# LED_Microcontroller_LED_schematic.net
KiCad netlist of a schematic drawn in Altium Designer
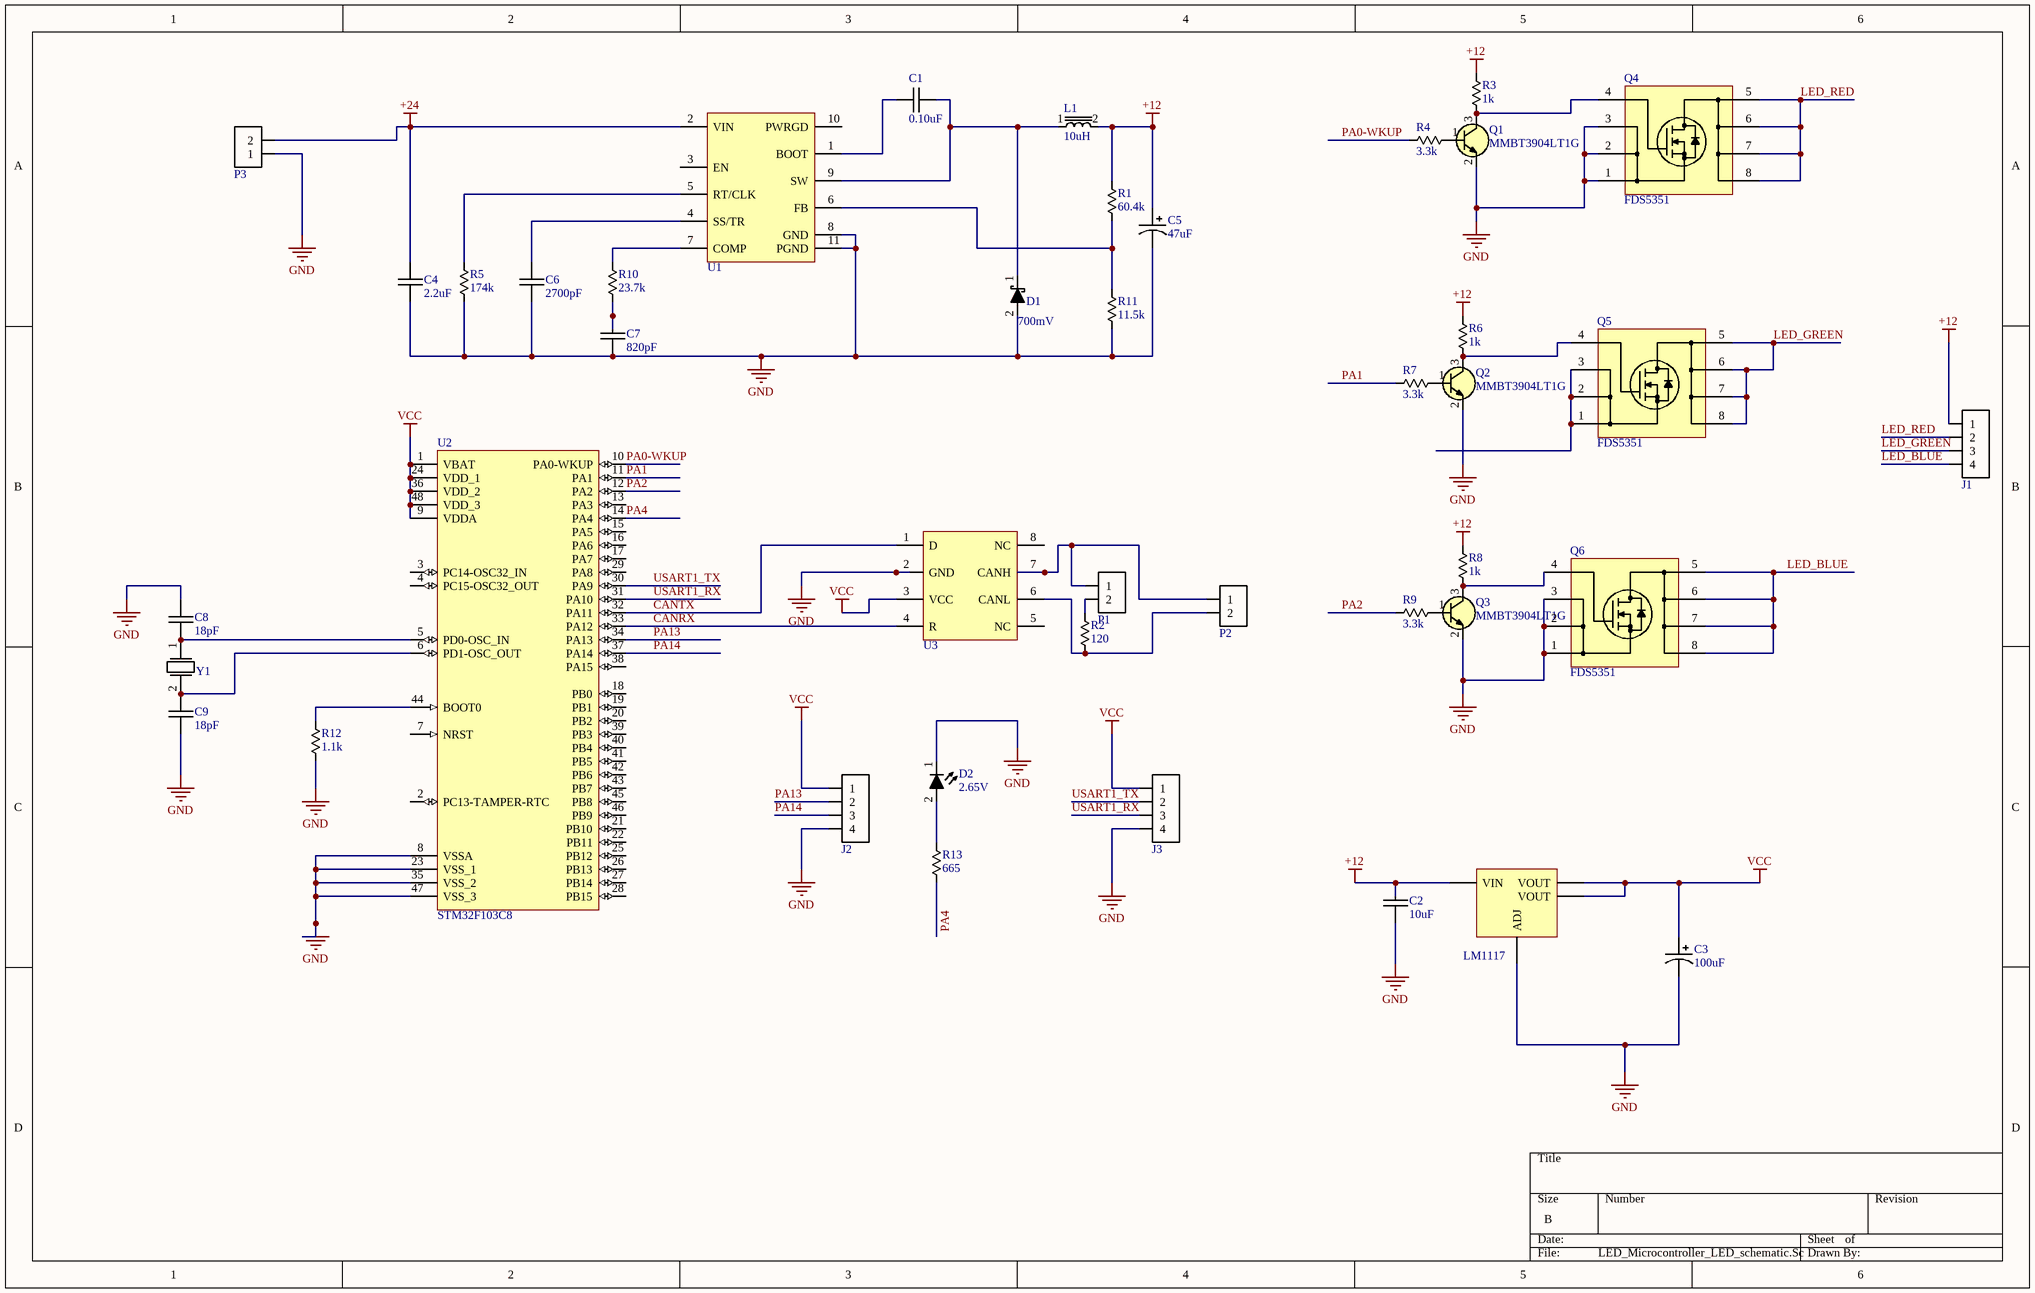
[diagram p0: LED_Microcontroller_LED_schematic.SchDoc]

(export (version "E")
  (design (tool "Eeschema 10.0.6"))
  (components
    (comp (ref "C1")
      (value "0.10uF")
      (footprint "chip_0805")
      (description "CAP, 0.10uF, 10%, 16V, X7R, 0805")
      (fields (field (name "PART NUMBER") "CAP-00069") (field (name "TOLERANCE") "10%"))
      (libsource (lib "Capacitors$") (part "CAP-00069"))
    )
    (comp (ref "C2")
      (value "10uF")
      (footprint "chip_1206")
      (description "CAP, 10uF, ±10%, 25V, X7R, 1206")
      (fields (field (name "PART NUMBER") "CAP-00539") (field (name "TOLERANCE") "±10%"))
      (libsource (lib "Capacitors$") (part "CAP-00539"))
    )
    (comp (ref "C3")
      (value "100uF")
      (footprint "chip_2917_AVX_TAJD")
      (description "CAP, 100uF, ±10%, 16V, Tantalum, 2917")
      (fields (field (name "PART NUMBER") "CAP-00550") (field (name "TOLERANCE") "±10%"))
      (libsource (lib "Capacitors$") (part "CAP-00550"))
    )
    (comp (ref "C4")
      (value "2.2uF")
      (footprint "chip_0603")
      (description "CAP, 2.2uF, ±10%, 10V, X7R, 0603")
      (fields (field (name "PART NUMBER") "CAP-00512") (field (name "TOLERANCE") "±10%"))
      (libsource (lib "Capacitors$") (part "CAP-00512"))
    )
    (comp (ref "C5")
      (value "47uF")
      (footprint "CP_NICHICON_UUX_10x10")
      (description "CAP, 47uF, ±20%, 100V, Al, SMD")
      (fields (field (name "PART NUMBER") "CAP-00567") (field (name "TOLERANCE") "±20%"))
      (libsource (lib "Capacitors$") (part "CAP-00567"))
    )
    (comp (ref "C6")
      (value "2700pF")
      (footprint "chip_0805")
      (description "CAP, 2700pF, 10%, 50V, X7R, 0805")
      (fields (field (name "PART NUMBER") "CAP-00024") (field (name "TOLERANCE") "10%"))
      (libsource (lib "Capacitors$") (part "CAP-00024"))
    )
    (comp (ref "C7")
      (value "820pF")
      (footprint "chip_0805")
      (description "CAP, 820pF, 10%, 50V, X7R, 0805")
      (fields (field (name "PART NUMBER") "CAP-00008") (field (name "TOLERANCE") "10%"))
      (libsource (lib "Capacitors$") (part "CAP-00008"))
    )
    (comp (ref "C8")
      (value "18pF")
      (footprint "chip_0603")
      (description "CAP, 18pF, ±2%, 50V, C0G, 0603")
      (fields (field (name "PART NUMBER") "CAP-00409") (field (name "TOLERANCE") "±2%"))
      (libsource (lib "Capacitors$") (part "CAP-00409"))
    )
    (comp (ref "C9")
      (value "18pF")
      (footprint "chip_0603")
      (description "CAP, 18pF, ±2%, 50V, C0G, 0603")
      (fields (field (name "PART NUMBER") "CAP-00409") (field (name "TOLERANCE") "±2%"))
      (libsource (lib "Capacitors$") (part "CAP-00409"))
    )
    (comp (ref "D1")
      (value "700mV")
      (footprint "do-214ab")
      (description "Dio, Schottky, 5A, 700mV, 60V, SMC")
      (fields (field (name "PART NUMBER") "DIO-00048") (field (name "MANUFACTURER") "Diodes Incorporated"))
      (libsource (lib "Diodes$") (part "DIO-00048"))
    )
    (comp (ref "D2")
      (value "2.65V")
      (footprint "chip_0603_LED")
      (description "LED, Green, 0603, Low current, HELI2 Series")
      (fields (field (name "PART NUMBER") "DIO-00050") (field (name "MANUFACTURER") "Kingbright"))
      (libsource (lib "Diodes$") (part "DIO-00050"))
    )
    (comp (ref "J1")
      (value "conn-4x1_0")
      (footprint "TERM_3.50MM_4x1_0")
      (description "Term Blk, 4 Pos, 8A, 3.5mm Pitch, Screwless")
      (fields (field (name "PART NUMBER") "CONN-00024") (field (name "MANUFACTURER") "Phoenix Contact"))
      (libsource (lib "Connectors$") (part "CONN-00024"))
    )
    (comp (ref "J2")
      (value "conn-4x1_0")
      (footprint "HDDR_4x1_0")
      (description "Header 4x1, 0.1\"")
      (fields (field (name "PART NUMBER") "CONN-00029"))
      (libsource (lib "Connectors$") (part "CONN-00029"))
    )
    (comp (ref "J3")
      (value "conn-4x1_0")
      (footprint "HDDR_4x1_0")
      (description "Header 4x1, 0.1\"")
      (fields (field (name "PART NUMBER") "CONN-00029"))
      (libsource (lib "Connectors$") (part "CONN-00029"))
    )
    (comp (ref "L1")
      (value "ind_1")
      (footprint "VISHAY_IHLP3232DZ")
      (description "Ind, 10uH, 20%, 5.2A (9A sat.), 0.0599 Ohm")
      (fields
        (field (name "PART NUMBER") "MAG-00106")
        (field (name "INDUCTANCE") "10uH")
        (field (name "TOLERANCE") "20%")
      )
      (libsource (lib "Magnetics$") (part "MAG-00106"))
    )
    (comp (ref "LM1117")
      (value "LM1117")
      (footprint "sot-223-4")
      (description "REG, Linear, Fixed 3V3, 800mA, SOT-223")
      (fields (field (name "PART NUMBER") "PWREG-00018") (field (name "MANUFACTURER") "TI"))
      (libsource (lib "Power Reg$") (part "PWREG-00018"))
    )
    (comp (ref "P1")
      (value "conn-2x1_0")
      (footprint "HDDR_2x1_0")
      (description "Header, 2x1, 0.1\"")
      (fields (field (name "PART NUMBER") "CONN-00055") (field (name "MANUFACTURER") "Samtec"))
      (libsource (lib "Connectors$") (part "CONN-00055"))
    )
    (comp (ref "P2")
      (value "conn-2x1_0")
      (footprint "TERM_3.50MM_2x1_0")
      (description "Term Blk, 2 Pos, 8A, 3.5mm Pitch, Screwless")
      (fields (field (name "PART NUMBER") "CONN-00023") (field (name "MANUFACTURER") "Phoenix Contact"))
      (libsource (lib "Connectors$") (part "CONN-00023"))
    )
    (comp (ref "P3")
      (value "conn-2x1_0")
      (footprint "TERM_3.50MM_2x1_0")
      (description "Term Blk, 2 Pos, 8A, 3.5mm Pitch, Screwless")
      (fields (field (name "PART NUMBER") "CONN-00023") (field (name "MANUFACTURER") "Phoenix Contact"))
      (libsource (lib "Connectors$") (part "CONN-00023"))
    )
    (comp (ref "Q1")
      (value "MMBT3904LT1G")
      (footprint "SOT-23-3_1")
      (description "XSTR, NPN, 200mA, 40V, Vce 0.3V, SOT-23-3")
      (fields (field (name "PART NUMBER") "XSTR-00037") (field (name "MANUFACTURER") "ON Semi"))
      (libsource (lib "Transistors$") (part "XSTR-00037"))
    )
    (comp (ref "Q2")
      (value "MMBT3904LT1G")
      (footprint "SOT-23-3_1")
      (description "XSTR, NPN, 200mA, 40V, Vce 0.3V, SOT-23-3")
      (fields (field (name "PART NUMBER") "XSTR-00037") (field (name "MANUFACTURER") "ON Semi"))
      (libsource (lib "Transistors$") (part "XSTR-00037"))
    )
    (comp (ref "Q3")
      (value "MMBT3904LT1G")
      (footprint "SOT-23-3_1")
      (description "XSTR, NPN, 200mA, 40V, Vce 0.3V, SOT-23-3")
      (fields (field (name "PART NUMBER") "XSTR-00037") (field (name "MANUFACTURER") "ON Semi"))
      (libsource (lib "Transistors$") (part "XSTR-00037"))
    )
    (comp (ref "Q4")
      (value "FDS5351")
      (footprint "SO-8")
      (description "XSTR NFET, 6.1A, 60V, 5W, SOIC-8")
      (fields (field (name "PART NUMBER") "XSTR-00034") (field (name "MANUFACTURER") "ON Semi"))
      (libsource (lib "Transistors$") (part "XSTR-00034"))
    )
    (comp (ref "Q5")
      (value "FDS5351")
      (footprint "SO-8")
      (description "XSTR NFET, 6.1A, 60V, 5W, SOIC-8")
      (fields (field (name "PART NUMBER") "XSTR-00034") (field (name "MANUFACTURER") "ON Semi"))
      (libsource (lib "Transistors$") (part "XSTR-00034"))
    )
    (comp (ref "Q6")
      (value "FDS5351")
      (footprint "SO-8")
      (description "XSTR NFET, 6.1A, 60V, 5W, SOIC-8")
      (fields (field (name "PART NUMBER") "XSTR-00034") (field (name "MANUFACTURER") "ON Semi"))
      (libsource (lib "Transistors$") (part "XSTR-00034"))
    )
    (comp (ref "R1")
      (value "60.4k")
      (footprint "chip_0805")
      (description "RES SMD 60.4K OHM 1% 1/8W 0805")
      (fields (field (name "PART NUMBER") "RES-00531") (field (name "TOLERANCE") "1%"))
      (libsource (lib "Resistors$") (part "RES-00531"))
    )
    (comp (ref "R2")
      (value "120")
      (footprint "chip_0805")
      (description "RES SMD 120 OHM 1% 1/8W 0805")
      (fields (field (name "PART NUMBER") "RES-00183") (field (name "TOLERANCE") "1%"))
      (libsource (lib "Resistors$") (part "RES-00183"))
    )
    (comp (ref "R3")
      (value "1k")
      (footprint "chip_0805")
      (description "RES SMD 1K OHM 1% 1/8W 0805")
      (fields (field (name "PART NUMBER") "RES-00361") (field (name "TOLERANCE") "1%"))
      (libsource (lib "Resistors$") (part "RES-00361"))
    )
    (comp (ref "R4")
      (value "3.3k")
      (footprint "chip_0603")
      (description "RES SMD 3.3K OHM 1% 1/4W 0603")
      (fields (field (name "PART NUMBER") "RES-00419") (field (name "TOLERANCE") "1%"))
      (libsource (lib "Resistors$") (part "RES-00419"))
    )
    (comp (ref "R5")
      (value "174k")
      (footprint "chip_0805")
      (description "RES SMD 174K OHM 1% 1/8W 0805")
      (fields (field (name "PART NUMBER") "RES-00350") (field (name "TOLERANCE") "1%"))
      (libsource (lib "Resistors$") (part "RES-00350"))
    )
    (comp (ref "R6")
      (value "1k")
      (footprint "chip_0805")
      (description "RES SMD 1K OHM 1% 1/8W 0805")
      (fields (field (name "PART NUMBER") "RES-00361") (field (name "TOLERANCE") "1%"))
      (libsource (lib "Resistors$") (part "RES-00361"))
    )
    (comp (ref "R7")
      (value "3.3k")
      (footprint "chip_0603")
      (description "RES SMD 3.3K OHM 1% 1/4W 0603")
      (fields (field (name "PART NUMBER") "RES-00419") (field (name "TOLERANCE") "1%"))
      (libsource (lib "Resistors$") (part "RES-00419"))
    )
    (comp (ref "R8")
      (value "1k")
      (footprint "chip_0805")
      (description "RES SMD 1K OHM 1% 1/8W 0805")
      (fields (field (name "PART NUMBER") "RES-00361") (field (name "TOLERANCE") "1%"))
      (libsource (lib "Resistors$") (part "RES-00361"))
    )
    (comp (ref "R9")
      (value "3.3k")
      (footprint "chip_0603")
      (description "RES SMD 3.3K OHM 1% 1/4W 0603")
      (fields (field (name "PART NUMBER") "RES-00419") (field (name "TOLERANCE") "1%"))
      (libsource (lib "Resistors$") (part "RES-00419"))
    )
    (comp (ref "R10")
      (value "23.7k")
      (footprint "chip_0805")
      (description "RES SMD 23.7K OHM 1% 1/8W 0805")
      (fields (field (name "PART NUMBER") "RES-00392") (field (name "TOLERANCE") "1%"))
      (libsource (lib "Resistors$") (part "RES-00392"))
    )
    (comp (ref "R11")
      (value "11.5k")
      (footprint "chip_0805")
      (description "RES SMD 11.5K OHM 1% 1/8W 0805")
      (fields (field (name "PART NUMBER") "RES-00309") (field (name "TOLERANCE") "1%"))
      (libsource (lib "Resistors$") (part "RES-00309"))
    )
    (comp (ref "R12")
      (value "1.1k")
      (footprint "chip_0603")
      (description "RES SMD 1.1K OHM 1% 1/4W 0603")
      (fields (field (name "PART NUMBER") "RES-00264") (field (name "TOLERANCE") "1%"))
      (libsource (lib "Resistors$") (part "RES-00264"))
    )
    (comp (ref "R13")
      (value "665")
      (footprint "chip_0805")
      (description "RES SMD 665 OHM 1% 1/8W 0805")
      (fields (field (name "PART NUMBER") "RES-00248") (field (name "TOLERANCE") "1%"))
      (libsource (lib "Resistors$") (part "RES-00248"))
    )
    (comp (ref "U1")
      (value "TPS54561")
      (footprint "WSON-10_0")
      (description "REG, SW Buck Adj, 5A, 4.5-60V, 2.5MHz, TPS54561")
      (fields (field (name "PART NUMBER") "PWREG-00033") (field (name "MANUFACTURER") "TI"))
      (libsource (lib "Power Reg$") (part "PWREG-00033"))
    )
    (comp (ref "U2")
      (value "STM32F103C8")
      (footprint "LQFP48_0")
      (description "STM32 M3, LQFP-48")
      (fields (field (name "PART NUMBER") "UCTRL-00008") (field (name "MANUFACTURER") "ST"))
      (libsource (lib "Microcontrollers$") (part "UCTRL-00008"))
    )
    (comp (ref "U3")
      (value "SN65HVD232")
      (footprint "SO-8")
      (description "CANbus Transceiver, Single channel, SN65HVD232")
      (fields (field (name "PART NUMBER") "IFACE-00008") (field (name "MANUFACTURER") "TI"))
      (libsource (lib "Interfaces$") (part "IFACE-00008"))
    )
    (comp (ref "Y1")
      (value "osc_xtal_2p_0")
      (footprint "ABLS_AT49_OSC")
      (description "XTAL, 8MHz, 18pF, 20ppm")
      (fields (field (name "PART NUMBER") "OSC-00002") (field (name "TOLERANCE") "20ppm"))
      (libsource (lib "Oscillators$") (part "OSC-00002"))
    )
  )
  (nets
    (net (code "1") (name "+12") (class "Default")
      (node (ref "C2") (pin "1") (pinfunction "1_1") (pintype "passive"))
      (node (ref "C5") (pin "1") (pinfunction "1_1") (pintype "passive"))
      (node (ref "J1") (pin "1") (pinfunction "1_1") (pintype "passive"))
      (node (ref "L1") (pin "2") (pinfunction "2_2") (pintype "passive"))
      (node (ref "LM1117") (pin "3") (pinfunction "VIN_3") (pintype "passive"))
      (node (ref "R1") (pin "1") (pinfunction "1_1") (pintype "passive"))
      (node (ref "R3") (pin "1") (pinfunction "1_1") (pintype "passive"))
      (node (ref "R6") (pin "1") (pinfunction "1_1") (pintype "passive"))
      (node (ref "R8") (pin "1") (pinfunction "1_1") (pintype "passive"))
    )
    (net (code "2") (name "+24") (class "Default")
      (node (ref "C4") (pin "1") (pinfunction "1_1") (pintype "passive"))
      (node (ref "P3") (pin "2") (pinfunction "2_2") (pintype "passive"))
      (node (ref "U1") (pin "2") (pinfunction "VIN_2") (pintype "passive"))
    )
    (net (code "3") (name "/CANRX") (class "Default")
      (node (ref "U2") (pin "33") (pinfunction "PA12_33") (pintype "bidirectional"))
      (node (ref "U3") (pin "4") (pinfunction "R_4") (pintype "passive"))
    )
    (net (code "4") (name "/CANTX") (class "Default")
      (node (ref "U2") (pin "32") (pinfunction "PA11_32") (pintype "bidirectional"))
      (node (ref "U3") (pin "1") (pinfunction "D_1") (pintype "passive"))
    )
    (net (code "5") (name "/LED_BLUE") (class "Default")
      (node (ref "J1") (pin "4") (pinfunction "4_4") (pintype "passive"))
      (node (ref "Q6") (pin "5") (pinfunction "D_5") (pintype "passive"))
      (node (ref "Q6") (pin "6") (pinfunction "D_6") (pintype "passive"))
      (node (ref "Q6") (pin "7") (pinfunction "D_7") (pintype "passive"))
      (node (ref "Q6") (pin "8") (pinfunction "D_8") (pintype "passive"))
    )
    (net (code "6") (name "/LED_GREEN") (class "Default")
      (node (ref "J1") (pin "3") (pinfunction "3_3") (pintype "passive"))
      (node (ref "Q5") (pin "5") (pinfunction "D_5") (pintype "passive"))
      (node (ref "Q5") (pin "6") (pinfunction "D_6") (pintype "passive"))
      (node (ref "Q5") (pin "7") (pinfunction "D_7") (pintype "passive"))
      (node (ref "Q5") (pin "8") (pinfunction "D_8") (pintype "passive"))
    )
    (net (code "7") (name "/LED_RED") (class "Default")
      (node (ref "J1") (pin "2") (pinfunction "2_2") (pintype "passive"))
      (node (ref "Q4") (pin "5") (pinfunction "D_5") (pintype "passive"))
      (node (ref "Q4") (pin "6") (pinfunction "D_6") (pintype "passive"))
      (node (ref "Q4") (pin "7") (pinfunction "D_7") (pintype "passive"))
      (node (ref "Q4") (pin "8") (pinfunction "D_8") (pintype "passive"))
    )
    (net (code "8") (name "/PA0-WKUP") (class "Default")
      (node (ref "R4") (pin "2") (pinfunction "2_2") (pintype "passive"))
      (node (ref "U2") (pin "10") (pinfunction "PA0-WKUP_10") (pintype "bidirectional"))
    )
    (net (code "9") (name "/PA1") (class "Default")
      (node (ref "R7") (pin "2") (pinfunction "2_2") (pintype "passive"))
      (node (ref "U2") (pin "11") (pinfunction "PA1_11") (pintype "bidirectional"))
    )
    (net (code "10") (name "/PA2") (class "Default")
      (node (ref "R9") (pin "2") (pinfunction "2_2") (pintype "passive"))
      (node (ref "U2") (pin "12") (pinfunction "PA2_12") (pintype "bidirectional"))
    )
    (net (code "11") (name "/PA4") (class "Default")
      (node (ref "R13") (pin "2") (pinfunction "2_2") (pintype "passive"))
      (node (ref "U2") (pin "14") (pinfunction "PA4_14") (pintype "bidirectional"))
    )
    (net (code "12") (name "/PA13") (class "Default")
      (node (ref "J2") (pin "2") (pinfunction "2_2") (pintype "passive"))
      (node (ref "U2") (pin "34") (pinfunction "PA13_34") (pintype "bidirectional"))
    )
    (net (code "13") (name "/PA14") (class "Default")
      (node (ref "J2") (pin "3") (pinfunction "3_3") (pintype "passive"))
      (node (ref "U2") (pin "37") (pinfunction "PA14_37") (pintype "bidirectional"))
    )
    (net (code "14") (name "/USART1_RX") (class "Default")
      (node (ref "J3") (pin "3") (pinfunction "3_3") (pintype "passive"))
      (node (ref "U2") (pin "31") (pinfunction "PA10_31") (pintype "bidirectional"))
    )
    (net (code "15") (name "/USART1_TX") (class "Default")
      (node (ref "J3") (pin "2") (pinfunction "2_2") (pintype "passive"))
      (node (ref "U2") (pin "30") (pinfunction "PA9_30") (pintype "bidirectional"))
    )
    (net (code "16") (name "GND") (class "Default")
      (node (ref "C2") (pin "2") (pinfunction "2_2") (pintype "passive"))
      (node (ref "C3") (pin "2") (pinfunction "2_2") (pintype "passive"))
      (node (ref "C4") (pin "2") (pinfunction "2_2") (pintype "passive"))
      (node (ref "C5") (pin "2") (pinfunction "2_2") (pintype "passive"))
      (node (ref "C6") (pin "2") (pinfunction "2_2") (pintype "passive"))
      (node (ref "C7") (pin "2") (pinfunction "2_2") (pintype "passive"))
      (node (ref "C8") (pin "1") (pinfunction "1_1") (pintype "passive"))
      (node (ref "C9") (pin "2") (pinfunction "2_2") (pintype "passive"))
      (node (ref "D1") (pin "2") (pinfunction "2_2") (pintype "passive"))
      (node (ref "D2") (pin "1") (pinfunction "1_1") (pintype "passive"))
      (node (ref "J2") (pin "4") (pinfunction "4_4") (pintype "passive"))
      (node (ref "J3") (pin "4") (pinfunction "4_4") (pintype "passive"))
      (node (ref "LM1117") (pin "1") (pinfunction "ADJ_1") (pintype "passive"))
      (node (ref "P3") (pin "1") (pinfunction "1_1") (pintype "passive"))
      (node (ref "Q1") (pin "2") (pinfunction "E_2") (pintype "passive"))
      (node (ref "Q2") (pin "2") (pinfunction "E_2") (pintype "passive"))
      (node (ref "Q3") (pin "2") (pinfunction "E_2") (pintype "passive"))
      (node (ref "Q4") (pin "1") (pinfunction "S_1") (pintype "passive"))
      (node (ref "Q4") (pin "2") (pinfunction "S_2") (pintype "passive"))
      (node (ref "Q4") (pin "3") (pinfunction "S_3") (pintype "passive"))
      (node (ref "Q6") (pin "1") (pinfunction "S_1") (pintype "passive"))
      (node (ref "Q6") (pin "2") (pinfunction "S_2") (pintype "passive"))
      (node (ref "Q6") (pin "3") (pinfunction "S_3") (pintype "passive"))
      (node (ref "R11") (pin "2") (pinfunction "2_2") (pintype "passive"))
      (node (ref "R12") (pin "2") (pinfunction "2_2") (pintype "passive"))
      (node (ref "R5") (pin "2") (pinfunction "2_2") (pintype "passive"))
      (node (ref "U1") (pin "11") (pinfunction "PGND_11") (pintype "passive"))
      (node (ref "U1") (pin "8") (pinfunction "GND_8") (pintype "passive"))
      (node (ref "U2") (pin "23") (pinfunction "VSS_1_23") (pintype "power_in"))
      (node (ref "U2") (pin "35") (pinfunction "VSS_2_35") (pintype "power_in"))
      (node (ref "U2") (pin "47") (pinfunction "VSS_3_47") (pintype "power_in"))
      (node (ref "U2") (pin "8") (pinfunction "VSSA_8") (pintype "power_in"))
      (node (ref "U3") (pin "2") (pinfunction "GND_2") (pintype "passive"))
    )
    (net (code "17") (name "Net-(C7-Pad1)") (class "Default")
      (node (ref "C7") (pin "1") (pinfunction "1_1") (pintype "passive"))
      (node (ref "R10") (pin "2") (pinfunction "2_2") (pintype "passive"))
    )
    (net (code "18") (name "Net-(D2-Pad2)") (class "Default")
      (node (ref "D2") (pin "2") (pinfunction "2_2") (pintype "passive"))
      (node (ref "R13") (pin "1") (pinfunction "1_1") (pintype "passive"))
    )
    (net (code "19") (name "Net-(P1-Pad2)") (class "Default")
      (node (ref "P1") (pin "2") (pinfunction "2_2") (pintype "passive"))
      (node (ref "R2") (pin "1") (pinfunction "1_1") (pintype "passive"))
    )
    (net (code "20") (name "Net-(Q1-B)") (class "Default")
      (node (ref "Q1") (pin "1") (pinfunction "B_1") (pintype "passive"))
      (node (ref "R4") (pin "1") (pinfunction "1_1") (pintype "passive"))
    )
    (net (code "21") (name "Net-(Q1-C)") (class "Default")
      (node (ref "Q1") (pin "3") (pinfunction "C_3") (pintype "passive"))
      (node (ref "Q4") (pin "4") (pinfunction "G_4") (pintype "passive"))
      (node (ref "R3") (pin "2") (pinfunction "2_2") (pintype "passive"))
    )
    (net (code "22") (name "Net-(Q2-B)") (class "Default")
      (node (ref "Q2") (pin "1") (pinfunction "B_1") (pintype "passive"))
      (node (ref "R7") (pin "1") (pinfunction "1_1") (pintype "passive"))
    )
    (net (code "23") (name "Net-(Q2-C)") (class "Default")
      (node (ref "Q2") (pin "3") (pinfunction "C_3") (pintype "passive"))
      (node (ref "Q5") (pin "4") (pinfunction "G_4") (pintype "passive"))
      (node (ref "R6") (pin "2") (pinfunction "2_2") (pintype "passive"))
    )
    (net (code "24") (name "Net-(Q3-B)") (class "Default")
      (node (ref "Q3") (pin "1") (pinfunction "B_1") (pintype "passive"))
      (node (ref "R9") (pin "1") (pinfunction "1_1") (pintype "passive"))
    )
    (net (code "25") (name "Net-(Q3-C)") (class "Default")
      (node (ref "Q3") (pin "3") (pinfunction "C_3") (pintype "passive"))
      (node (ref "Q6") (pin "4") (pinfunction "G_4") (pintype "passive"))
      (node (ref "R8") (pin "2") (pinfunction "2_2") (pintype "passive"))
    )
    (net (code "26") (name "Net-(Q5-S-Pad1)") (class "Default")
      (node (ref "Q5") (pin "1") (pinfunction "S_1") (pintype "passive"))
      (node (ref "Q5") (pin "2") (pinfunction "S_2") (pintype "passive"))
      (node (ref "Q5") (pin "3") (pinfunction "S_3") (pintype "passive"))
    )
    (net (code "27") (name "Net-(U1-BOOT)") (class "Default")
      (node (ref "C1") (pin "2") (pinfunction "2_2") (pintype "passive"))
      (node (ref "U1") (pin "1") (pinfunction "BOOT_1") (pintype "passive"))
    )
    (net (code "28") (name "Net-(U1-COMP)") (class "Default")
      (node (ref "R10") (pin "1") (pinfunction "1_1") (pintype "passive"))
      (node (ref "U1") (pin "7") (pinfunction "COMP_7") (pintype "passive"))
    )
    (net (code "29") (name "Net-(U1-FB)") (class "Default")
      (node (ref "R1") (pin "2") (pinfunction "2_2") (pintype "passive"))
      (node (ref "R11") (pin "1") (pinfunction "1_1") (pintype "passive"))
      (node (ref "U1") (pin "6") (pinfunction "FB_6") (pintype "passive"))
    )
    (net (code "30") (name "Net-(U1-RT{slash}CLK)") (class "Default")
      (node (ref "R5") (pin "1") (pinfunction "1_1") (pintype "passive"))
      (node (ref "U1") (pin "5") (pinfunction "RT/CLK_5") (pintype "passive"))
    )
    (net (code "31") (name "Net-(U1-SS{slash}TR)") (class "Default")
      (node (ref "C6") (pin "1") (pinfunction "1_1") (pintype "passive"))
      (node (ref "U1") (pin "4") (pinfunction "SS/TR_4") (pintype "passive"))
    )
    (net (code "32") (name "Net-(U1-SW)") (class "Default")
      (node (ref "C1") (pin "1") (pinfunction "1_1") (pintype "passive"))
      (node (ref "D1") (pin "1") (pinfunction "1_1") (pintype "passive"))
      (node (ref "L1") (pin "1") (pinfunction "1_1") (pintype "passive"))
      (node (ref "U1") (pin "9") (pinfunction "SW_9") (pintype "passive"))
    )
    (net (code "33") (name "Net-(U2-BOOT0)") (class "Default")
      (node (ref "R12") (pin "1") (pinfunction "1_1") (pintype "passive"))
      (node (ref "U2") (pin "44") (pinfunction "BOOT0_44") (pintype "input"))
    )
    (net (code "34") (name "Net-(U2-PD0-OSC_IN)") (class "Default")
      (node (ref "C8") (pin "2") (pinfunction "2_2") (pintype "passive"))
      (node (ref "U2") (pin "5") (pinfunction "PD0-OSC_IN_5") (pintype "bidirectional"))
      (node (ref "Y1") (pin "1") (pinfunction "20_1") (pintype "passive"))
    )
    (net (code "35") (name "Net-(U2-PD1-OSC_OUT)") (class "Default")
      (node (ref "C9") (pin "1") (pinfunction "1_1") (pintype "passive"))
      (node (ref "U2") (pin "6") (pinfunction "PD1-OSC_OUT_6") (pintype "bidirectional"))
      (node (ref "Y1") (pin "2") (pinfunction "20_2") (pintype "passive"))
    )
    (net (code "36") (name "Net-(U3-CANH)") (class "Default")
      (node (ref "P1") (pin "1") (pinfunction "1_1") (pintype "passive"))
      (node (ref "P2") (pin "1") (pinfunction "1_1") (pintype "passive"))
      (node (ref "U3") (pin "7") (pinfunction "CANH_7") (pintype "passive"))
    )
    (net (code "37") (name "Net-(U3-CANL)") (class "Default")
      (node (ref "P2") (pin "2") (pinfunction "2_2") (pintype "passive"))
      (node (ref "R2") (pin "2") (pinfunction "2_2") (pintype "passive"))
      (node (ref "U3") (pin "6") (pinfunction "CANL_6") (pintype "passive"))
    )
    (net (code "38") (name "VCC") (class "Default")
      (node (ref "C3") (pin "1") (pinfunction "1_1") (pintype "passive"))
      (node (ref "J2") (pin "1") (pinfunction "1_1") (pintype "passive"))
      (node (ref "J3") (pin "1") (pinfunction "1_1") (pintype "passive"))
      (node (ref "LM1117") (pin "2") (pinfunction "VOUT_2") (pintype "passive"))
      (node (ref "LM1117") (pin "4") (pinfunction "VOUT_4") (pintype "passive"))
      (node (ref "U2") (pin "1") (pinfunction "VBAT_1") (pintype "passive"))
      (node (ref "U2") (pin "24") (pinfunction "VDD_1_24") (pintype "power_in"))
      (node (ref "U2") (pin "36") (pinfunction "VDD_2_36") (pintype "power_in"))
      (node (ref "U2") (pin "48") (pinfunction "VDD_3_48") (pintype "power_in"))
      (node (ref "U2") (pin "9") (pinfunction "VDDA_9") (pintype "power_in"))
      (node (ref "U3") (pin "3") (pinfunction "VCC_3") (pintype "passive"))
    )
    (net (code "39") (name "unconnected-(U1-EN-Pad3)") (class "Default")
      (node (ref "U1") (pin "3") (pinfunction "EN_3") (pintype "passive"))
    )
    (net (code "40") (name "unconnected-(U1-PWRGD-Pad10)") (class "Default")
      (node (ref "U1") (pin "10") (pinfunction "PWRGD_10") (pintype "passive"))
    )
    (net (code "41") (name "unconnected-(U2-NRST-Pad7)") (class "Default")
      (node (ref "U2") (pin "7") (pinfunction "NRST_7") (pintype "input"))
    )
    (net (code "42") (name "unconnected-(U2-PA3-Pad13)") (class "Default")
      (node (ref "U2") (pin "13") (pinfunction "PA3_13") (pintype "bidirectional"))
    )
    (net (code "43") (name "unconnected-(U2-PA5-Pad15)") (class "Default")
      (node (ref "U2") (pin "15") (pinfunction "PA5_15") (pintype "bidirectional"))
    )
    (net (code "44") (name "unconnected-(U2-PA6-Pad16)") (class "Default")
      (node (ref "U2") (pin "16") (pinfunction "PA6_16") (pintype "bidirectional"))
    )
    (net (code "45") (name "unconnected-(U2-PA7-Pad17)") (class "Default")
      (node (ref "U2") (pin "17") (pinfunction "PA7_17") (pintype "bidirectional"))
    )
    (net (code "46") (name "unconnected-(U2-PA8-Pad29)") (class "Default")
      (node (ref "U2") (pin "29") (pinfunction "PA8_29") (pintype "bidirectional"))
    )
    (net (code "47") (name "unconnected-(U2-PA15-Pad38)") (class "Default")
      (node (ref "U2") (pin "38") (pinfunction "PA15_38") (pintype "bidirectional"))
    )
    (net (code "48") (name "unconnected-(U2-PB0-Pad18)") (class "Default")
      (node (ref "U2") (pin "18") (pinfunction "PB0_18") (pintype "bidirectional"))
    )
    (net (code "49") (name "unconnected-(U2-PB1-Pad19)") (class "Default")
      (node (ref "U2") (pin "19") (pinfunction "PB1_19") (pintype "bidirectional"))
    )
    (net (code "50") (name "unconnected-(U2-PB2-Pad20)") (class "Default")
      (node (ref "U2") (pin "20") (pinfunction "PB2_20") (pintype "bidirectional"))
    )
    (net (code "51") (name "unconnected-(U2-PB3-Pad39)") (class "Default")
      (node (ref "U2") (pin "39") (pinfunction "PB3_39") (pintype "bidirectional"))
    )
    (net (code "52") (name "unconnected-(U2-PB4-Pad40)") (class "Default")
      (node (ref "U2") (pin "40") (pinfunction "PB4_40") (pintype "bidirectional"))
    )
    (net (code "53") (name "unconnected-(U2-PB5-Pad41)") (class "Default")
      (node (ref "U2") (pin "41") (pinfunction "PB5_41") (pintype "bidirectional"))
    )
    (net (code "54") (name "unconnected-(U2-PB6-Pad42)") (class "Default")
      (node (ref "U2") (pin "42") (pinfunction "PB6_42") (pintype "bidirectional"))
    )
    (net (code "55") (name "unconnected-(U2-PB7-Pad43)") (class "Default")
      (node (ref "U2") (pin "43") (pinfunction "PB7_43") (pintype "bidirectional"))
    )
    (net (code "56") (name "unconnected-(U2-PB8-Pad45)") (class "Default")
      (node (ref "U2") (pin "45") (pinfunction "PB8_45") (pintype "bidirectional"))
    )
    (net (code "57") (name "unconnected-(U2-PB9-Pad46)") (class "Default")
      (node (ref "U2") (pin "46") (pinfunction "PB9_46") (pintype "bidirectional"))
    )
    (net (code "58") (name "unconnected-(U2-PB10-Pad21)") (class "Default")
      (node (ref "U2") (pin "21") (pinfunction "PB10_21") (pintype "bidirectional"))
    )
    (net (code "59") (name "unconnected-(U2-PB11-Pad22)") (class "Default")
      (node (ref "U2") (pin "22") (pinfunction "PB11_22") (pintype "bidirectional"))
    )
    (net (code "60") (name "unconnected-(U2-PB12-Pad25)") (class "Default")
      (node (ref "U2") (pin "25") (pinfunction "PB12_25") (pintype "bidirectional"))
    )
    (net (code "61") (name "unconnected-(U2-PB13-Pad26)") (class "Default")
      (node (ref "U2") (pin "26") (pinfunction "PB13_26") (pintype "bidirectional"))
    )
    (net (code "62") (name "unconnected-(U2-PB14-Pad27)") (class "Default")
      (node (ref "U2") (pin "27") (pinfunction "PB14_27") (pintype "bidirectional"))
    )
    (net (code "63") (name "unconnected-(U2-PB15-Pad28)") (class "Default")
      (node (ref "U2") (pin "28") (pinfunction "PB15_28") (pintype "bidirectional"))
    )
    (net (code "64") (name "unconnected-(U2-PC13-TAMPER-RTC-Pad2)") (class "Default")
      (node (ref "U2") (pin "2") (pinfunction "PC13-TAMPER-RTC_2") (pintype "bidirectional"))
    )
    (net (code "65") (name "unconnected-(U2-PC14-OSC32_IN-Pad3)") (class "Default")
      (node (ref "U2") (pin "3") (pinfunction "PC14-OSC32_IN_3") (pintype "bidirectional"))
    )
    (net (code "66") (name "unconnected-(U2-PC15-OSC32_OUT-Pad4)") (class "Default")
      (node (ref "U2") (pin "4") (pinfunction "PC15-OSC32_OUT_4") (pintype "bidirectional"))
    )
    (net (code "67") (name "unconnected-(U3-NC-Pad5)") (class "Default")
      (node (ref "U3") (pin "5") (pinfunction "NC_5") (pintype "passive"))
    )
    (net (code "68") (name "unconnected-(U3-NC-Pad8)") (class "Default")
      (node (ref "U3") (pin "8") (pinfunction "NC_8") (pintype "passive"))
    )
  )
)
